# PoE.net
KiCad netlist of a schematic drawn in EAGLE
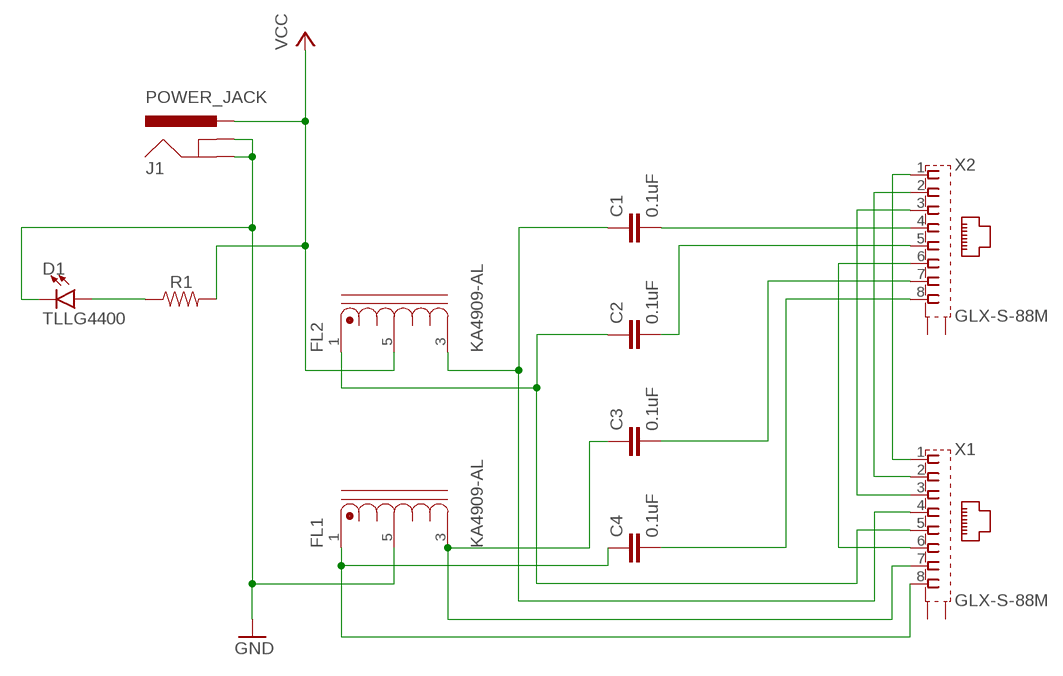
[diagram p0: schematic, sheet 1]

(export (version "E")
  (design (tool "Eeschema 10.0.6"))
  (components
    (comp (ref "C1")
      (value "0.1uF")
      (footprint "eagle-import:CAP-PTH-SMALL-KIT")
      (libsource (lib "eagle-import") (part "0.1UF-KIT-EZ-50V-20%"))
    )
    (comp (ref "C2")
      (value "0.1uF")
      (footprint "eagle-import:CAP-PTH-SMALL-KIT")
      (libsource (lib "eagle-import") (part "0.1UF-KIT-EZ-50V-20%"))
    )
    (comp (ref "C3")
      (value "0.1uF")
      (footprint "eagle-import:CAP-PTH-SMALL-KIT")
      (libsource (lib "eagle-import") (part "0.1UF-KIT-EZ-50V-20%"))
    )
    (comp (ref "C4")
      (value "0.1uF")
      (footprint "eagle-import:CAP-PTH-SMALL-KIT")
      (libsource (lib "eagle-import") (part "0.1UF-KIT-EZ-50V-20%"))
    )
    (comp (ref "D1")
      (value "TLLG4400")
      (footprint "eagle-import:LED_3MM")
      (libsource (lib "eagle-import") (part "LED3MM"))
    )
    (comp (ref "FL1")
      (value "KA4909-AL")
      (footprint "eagle-import:FIL_KA4909-AL")
      (fields (field (name "MF") "Coilcraft"))
      (libsource (lib "eagle-import") (part "KA4909-AL"))
    )
    (comp (ref "FL2")
      (value "KA4909-AL")
      (footprint "eagle-import:FIL_KA4909-AL")
      (fields (field (name "MF") "Coilcraft"))
      (libsource (lib "eagle-import") (part "KA4909-AL"))
    )
    (comp (ref "J1")
      (value "POWER_JACK")
      (footprint "eagle-import:POWER_JACK_PTH")
      (libsource (lib "eagle-import") (part "POWER_JACK"))
    )
    (comp (ref "R1")
      (value "RESISTORAXIAL-0.3")
      (footprint "eagle-import:AXIAL-0.3")
      (libsource (lib "eagle-import") (part "RESISTORAXIAL-0.3"))
    )
    (comp (ref "X1")
      (value "GLX-S-88M")
      (footprint "eagle-import:GLX-S-88M")
      (libsource (lib "eagle-import") (part "GLX-S-88M"))
    )
    (comp (ref "X2")
      (value "GLX-S-88M")
      (footprint "eagle-import:GLX-S-88M")
      (libsource (lib "eagle-import") (part "GLX-S-88M"))
    )
  )
  (nets
    (net (code "1") (name "GND") (class "Default")
      (node (ref "D1") (pin "K") (pinfunction "C_K") (pintype "passive"))
      (node (ref "FL1") (pin "5") (pinfunction "5_5") (pintype "passive"))
      (node (ref "J1") (pin "GND") (pinfunction "GND_GND") (pintype "bidirectional"))
      (node (ref "J1") (pin "GNDBREAK") (pinfunction "GNDBREAK_GNDBREAK") (pintype "bidirectional"))
    )
    (net (code "2") (name "Net-(C1-Pad1)") (class "Default")
      (node (ref "C1") (pin "1") (pinfunction "1_1") (pintype "passive"))
      (node (ref "FL2") (pin "3") (pinfunction "3_3") (pintype "passive"))
      (node (ref "X1") (pin "4") (pinfunction "4_4") (pintype "passive"))
    )
    (net (code "3") (name "Net-(C1-Pad2)") (class "Default")
      (node (ref "C1") (pin "2") (pinfunction "2_2") (pintype "passive"))
      (node (ref "X2") (pin "4") (pinfunction "4_4") (pintype "passive"))
    )
    (net (code "4") (name "Net-(C2-Pad1)") (class "Default")
      (node (ref "C2") (pin "1") (pinfunction "1_1") (pintype "passive"))
      (node (ref "FL2") (pin "1") (pinfunction "1_1") (pintype "passive"))
      (node (ref "X1") (pin "5") (pinfunction "5_5") (pintype "passive"))
    )
    (net (code "5") (name "Net-(C2-Pad2)") (class "Default")
      (node (ref "C2") (pin "2") (pinfunction "2_2") (pintype "passive"))
      (node (ref "X2") (pin "5") (pinfunction "5_5") (pintype "passive"))
    )
    (net (code "6") (name "Net-(C3-Pad1)") (class "Default")
      (node (ref "C3") (pin "1") (pinfunction "1_1") (pintype "passive"))
      (node (ref "FL1") (pin "3") (pinfunction "3_3") (pintype "passive"))
      (node (ref "X1") (pin "7") (pinfunction "7_7") (pintype "passive"))
    )
    (net (code "7") (name "Net-(C3-Pad2)") (class "Default")
      (node (ref "C3") (pin "2") (pinfunction "2_2") (pintype "passive"))
      (node (ref "X2") (pin "7") (pinfunction "7_7") (pintype "passive"))
    )
    (net (code "8") (name "Net-(C4-Pad1)") (class "Default")
      (node (ref "C4") (pin "1") (pinfunction "1_1") (pintype "passive"))
      (node (ref "FL1") (pin "1") (pinfunction "1_1") (pintype "passive"))
      (node (ref "X1") (pin "8") (pinfunction "8_8") (pintype "passive"))
    )
    (net (code "9") (name "Net-(C4-Pad2)") (class "Default")
      (node (ref "C4") (pin "2") (pinfunction "2_2") (pintype "passive"))
      (node (ref "X2") (pin "8") (pinfunction "8_8") (pintype "passive"))
    )
    (net (code "10") (name "Net-(R1-1)") (class "Default")
      (node (ref "D1") (pin "A") (pinfunction "A_A") (pintype "passive"))
      (node (ref "R1") (pin "P$1") (pinfunction "1_P$1") (pintype "passive"))
    )
    (net (code "11") (name "Net-(X1-Pad1)") (class "Default")
      (node (ref "X1") (pin "1") (pinfunction "1_1") (pintype "passive"))
      (node (ref "X2") (pin "1") (pinfunction "1_1") (pintype "passive"))
    )
    (net (code "12") (name "Net-(X1-Pad2)") (class "Default")
      (node (ref "X1") (pin "2") (pinfunction "2_2") (pintype "passive"))
      (node (ref "X2") (pin "2") (pinfunction "2_2") (pintype "passive"))
    )
    (net (code "13") (name "Net-(X1-Pad3)") (class "Default")
      (node (ref "X1") (pin "3") (pinfunction "3_3") (pintype "passive"))
      (node (ref "X2") (pin "3") (pinfunction "3_3") (pintype "passive"))
    )
    (net (code "14") (name "Net-(X1-Pad6)") (class "Default")
      (node (ref "X1") (pin "6") (pinfunction "6_6") (pintype "passive"))
      (node (ref "X2") (pin "6") (pinfunction "6_6") (pintype "passive"))
    )
    (net (code "15") (name "VCC") (class "Default")
      (node (ref "FL2") (pin "5") (pinfunction "5_5") (pintype "passive"))
      (node (ref "J1") (pin "PWR") (pinfunction "PWR_PWR") (pintype "bidirectional"))
      (node (ref "R1") (pin "P$2") (pinfunction "2_P$2") (pintype "passive"))
    )
    (net (code "16") (name "unconnected-(X1-PadS1)") (class "Default")
      (node (ref "X1") (pin "S1") (pinfunction "S1_S1") (pintype "passive"))
    )
    (net (code "17") (name "unconnected-(X1-PadS2)") (class "Default")
      (node (ref "X1") (pin "S2") (pinfunction "S2_S2") (pintype "passive"))
    )
    (net (code "18") (name "unconnected-(X2-PadS1)") (class "Default")
      (node (ref "X2") (pin "S1") (pinfunction "S1_S1") (pintype "passive"))
    )
    (net (code "19") (name "unconnected-(X2-PadS2)") (class "Default")
      (node (ref "X2") (pin "S2") (pinfunction "S2_S2") (pintype "passive"))
    )
  )
)
